# BLHP2432_H24-Fan-Controller.net
KiCad netlist of a schematic drawn in Altium Designer
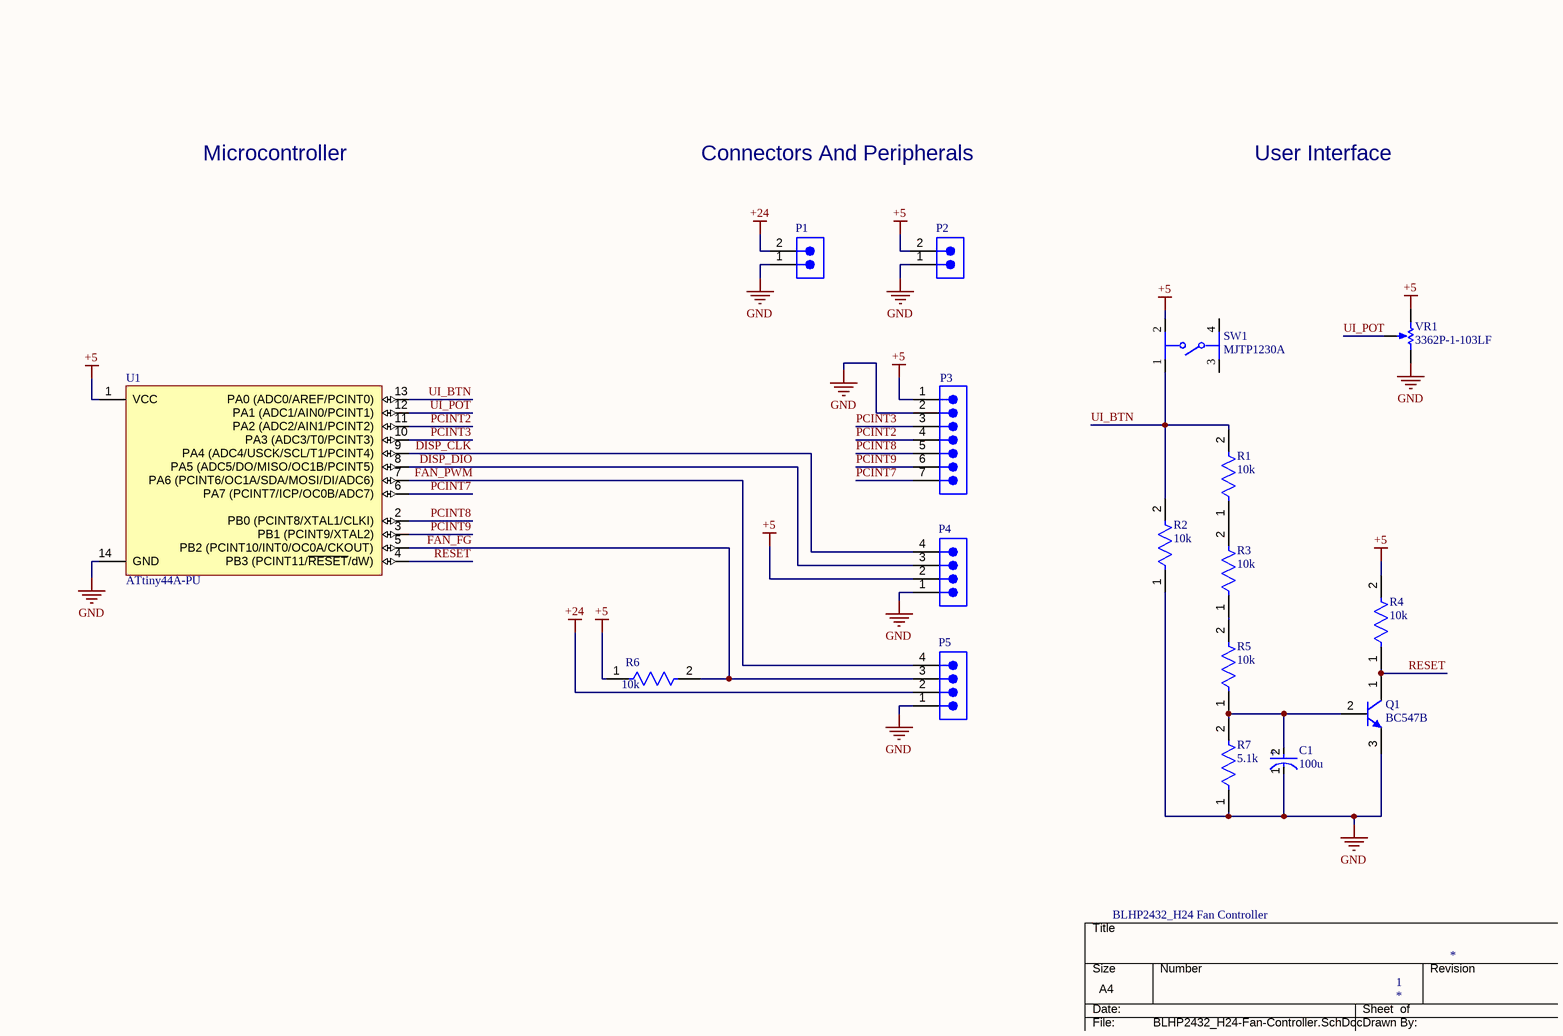
[diagram p0: BLHP2432_H24-Fan-Controller.SchDoc]

(export (version "E")
  (design (tool "Eeschema 10.0.6"))
  (components
    (comp (ref "C1")
      (value "100u")
      (footprint "FP-UHW1E222MHD-MFG")
      (description "CAP ALUM 2200UF 20% 25V RADIAL")
      (fields (field (name "TOLERANCE") "20%"))
      (libsource (lib "Altium Content Vault") (part "203bc49f2ac43e59fd269a8c329ed05"))
    )
    (comp (ref "P1")
      (value "TSW-102-26-G-S")
      (footprint "SMTC-TSW-102-26-XX-S")
      (description "0.025\" SQ Post Header, Through-hole, Vertical, -55 to 125 degC, 2.54 mm Pitch, 2-Pin, Male, RoHS")
      (fields (field (name "MANUFACTURER") "Samtec"))
      (libsource (lib "Altium Content Vault") (part "SMTC-TSW-102-X-X-S-X"))
    )
    (comp (ref "P2")
      (value "TSW-102-26-G-S")
      (footprint "SMTC-TSW-102-26-XX-S")
      (description "0.025\" SQ Post Header, Through-hole, Vertical, -55 to 125 degC, 2.54 mm Pitch, 2-Pin, Male, RoHS")
      (fields (field (name "MANUFACTURER") "Samtec"))
      (libsource (lib "Altium Content Vault") (part "SMTC-TSW-102-X-X-S-X"))
    )
    (comp (ref "P3")
      (value "61300711021")
      (footprint "61300711021")
      (description "THT Angled Pin Header WR-PHD, Pitch 2.54 mm, Single Row, 7 pins")
      (libsource (lib "Altium Content Vault") (part "Header_Male_1R_07P"))
    )
    (comp (ref "P4")
      (value "~")
      (footprint "SMTC-TSW-104-08-X-S")
      (description "0.025\" SQ Post Header, Through-hole, Vertical, -55 to 125 degC, 2.54 mm Pitch, 4-Pin, Male, RoHS")
      (fields (field (name "MANUFACTURER") "Samtec") (field (name "PARTNUMBER") "TSW-104-08-G-S"))
      (libsource (lib "Altium Content Vault") (part "SMTC-TSW-104-08-X-S"))
    )
    (comp (ref "P5")
      (value "~")
      (footprint "SMTC-TSW-104-08-X-S")
      (description "0.025\" SQ Post Header, Through-hole, Vertical, -55 to 125 degC, 2.54 mm Pitch, 4-Pin, Male, RoHS")
      (fields (field (name "MANUFACTURER") "Samtec") (field (name "PARTNUMBER") "TSW-104-08-G-S"))
      (libsource (lib "Altium Content Vault") (part "SMTC-TSW-104-08-X-S"))
    )
    (comp (ref "Q1")
      (value "BC547B")
      (footprint "ONSC-TO-92-3-29-11")
      (description "Amplifier Transistor, NPN Silicon, 3-Pin TO-92, Bulk Box")
      (fields (field (name "MANUFACTURER") "On Semiconductor"))
      (libsource (lib "Altium Content Vault") (part "ONSC-NPN-C1B2E3-3"))
    )
    (comp (ref "R1")
      (value "10k")
      (footprint "FP-MBB0207-MFG")
      (description "RES 10K OHM 0.6W 1% AXIAL")
      (fields (field (name "TOLERANCE") "1%"))
      (libsource (lib "Altium Content Vault") (part "1029c3af85768c4190bb7ad29bc67b5"))
    )
    (comp (ref "R2")
      (value "10k")
      (footprint "FP-MBB0207-MFG")
      (description "RES 10K OHM 0.6W 1% AXIAL")
      (fields (field (name "TOLERANCE") "1%"))
      (libsource (lib "Altium Content Vault") (part "1029c3af85768c4190bb7ad29bc67b5"))
    )
    (comp (ref "R3")
      (value "10k")
      (footprint "FP-MBB0207-MFG")
      (description "RES 10K OHM 0.6W 1% AXIAL")
      (fields (field (name "TOLERANCE") "1%"))
      (libsource (lib "Altium Content Vault") (part "1029c3af85768c4190bb7ad29bc67b5"))
    )
    (comp (ref "R4")
      (value "10k")
      (footprint "FP-MBB0207-MFG")
      (description "RES 10K OHM 0.6W 1% AXIAL")
      (fields (field (name "TOLERANCE") "1%"))
      (libsource (lib "Altium Content Vault") (part "1029c3af85768c4190bb7ad29bc67b5"))
    )
    (comp (ref "R5")
      (value "10k")
      (footprint "FP-MBB0207-MFG")
      (description "RES 10K OHM 0.6W 1% AXIAL")
      (fields (field (name "TOLERANCE") "1%"))
      (libsource (lib "Altium Content Vault") (part "1029c3af85768c4190bb7ad29bc67b5"))
    )
    (comp (ref "R6")
      (value "10k")
      (footprint "FP-MBB0207-MFG")
      (description "RES 10K OHM 0.6W 1% AXIAL")
      (fields (field (name "TOLERANCE") "1%"))
      (libsource (lib "Altium Content Vault") (part "1029c3af85768c4190bb7ad29bc67b5"))
    )
    (comp (ref "R7")
      (value "5.1k")
      (footprint "FP-MBB0207-MFG")
      (description "RES 10K OHM 0.6W 1% AXIAL")
      (fields (field (name "TOLERANCE") "1%"))
      (libsource (lib "Altium Content Vault") (part "1029c3af85768c4190bb7ad29bc67b5"))
    )
    (comp (ref "SW1")
      (value "MJTP1230A")
      (footprint "FP-MJTP1230A-MFG")
      (description "SWITCH TACTILE SPST-NO 0.05A 12V")
      (libsource (lib "Altium Content Vault") (part "1adf0dd01260c80cf25a44bfd6b99ba"))
    )
    (comp (ref "U1")
      (value "ATtiny44A-PU")
      (footprint "14P3")
      (libsource (lib "Altium Content Vault") (part "MC-8B-ATTINY24V-IL14"))
    )
    (comp (ref "VR1")
      (value "3362P-1-103LF")
      (footprint "BOUR-3362P")
      (description "Square Trimpot(R) Trimming Potentiometer, 10 KOhm, 300 V, -55 to 125 degC, 3-Pin THD, RoHS, Tube")
      (fields (field (name "TOLERANCE") "1%"))
      (libsource (lib "Altium Content Vault") (part "RES-POT-3"))
    )
  )
  (nets
    (net (code "1") (name "+5") (class "Default")
      (node (ref "P2") (pin "2") (pinfunction "2_2") (pintype "passive"))
      (node (ref "P3") (pin "1") (pinfunction "1_1") (pintype "passive"))
      (node (ref "P4") (pin "2") (pinfunction "2_2") (pintype "passive"))
      (node (ref "R4") (pin "2") (pinfunction "2_2") (pintype "passive"))
      (node (ref "R6") (pin "1") (pinfunction "1_1") (pintype "passive"))
      (node (ref "SW1") (pin "2") (pinfunction "2_2") (pintype "passive"))
      (node (ref "U1") (pin "1") (pinfunction "VCC_1") (pintype "power_in"))
      (node (ref "VR1") (pin "1") (pinfunction "CCW_1") (pintype "passive"))
    )
    (net (code "2") (name "+24") (class "Default")
      (node (ref "P1") (pin "2") (pinfunction "2_2") (pintype "passive"))
      (node (ref "P5") (pin "2") (pinfunction "2_2") (pintype "passive"))
    )
    (net (code "3") (name "/DISP_CLK") (class "Default")
      (node (ref "P4") (pin "4") (pinfunction "4_4") (pintype "passive"))
      (node (ref "U1") (pin "9") (pinfunction "PA4_(ADC4/USCK/SCL/T1/PCINT4)_9") (pintype "bidirectional"))
    )
    (net (code "4") (name "/DISP_DIO") (class "Default")
      (node (ref "P4") (pin "3") (pinfunction "3_3") (pintype "passive"))
      (node (ref "U1") (pin "8") (pinfunction "PA5_(ADC5/DO/MISO/OC1B/PCINT5)_8") (pintype "bidirectional"))
    )
    (net (code "5") (name "/FAN_FG") (class "Default")
      (node (ref "P5") (pin "3") (pinfunction "3_3") (pintype "passive"))
      (node (ref "R6") (pin "2") (pinfunction "2_2") (pintype "passive"))
      (node (ref "U1") (pin "5") (pinfunction "PB2_(PCINT10/INT0/OC0A/CKOUT)_5") (pintype "bidirectional"))
    )
    (net (code "6") (name "/FAN_PWM") (class "Default")
      (node (ref "P5") (pin "4") (pinfunction "4_4") (pintype "passive"))
      (node (ref "U1") (pin "7") (pinfunction "PA6_(PCINT6/OC1A/SDA/MOSI/DI/ADC6)_7") (pintype "bidirectional"))
    )
    (net (code "7") (name "/PCINT2") (class "Default")
      (node (ref "P3") (pin "4") (pinfunction "4_4") (pintype "passive"))
      (node (ref "U1") (pin "11") (pinfunction "PA2_(ADC2/AIN1/PCINT2)_11") (pintype "bidirectional"))
    )
    (net (code "8") (name "/PCINT3") (class "Default")
      (node (ref "P3") (pin "3") (pinfunction "3_3") (pintype "passive"))
      (node (ref "U1") (pin "10") (pinfunction "PA3_(ADC3/T0/PCINT3)_10") (pintype "bidirectional"))
    )
    (net (code "9") (name "/PCINT7") (class "Default")
      (node (ref "P3") (pin "7") (pinfunction "7_7") (pintype "passive"))
      (node (ref "U1") (pin "6") (pinfunction "PA7_(PCINT7/ICP/OC0B/ADC7)_6") (pintype "bidirectional"))
    )
    (net (code "10") (name "/PCINT8") (class "Default")
      (node (ref "P3") (pin "5") (pinfunction "5_5") (pintype "passive"))
      (node (ref "U1") (pin "2") (pinfunction "PB0_(PCINT8/XTAL1/CLKI)_2") (pintype "bidirectional"))
    )
    (net (code "11") (name "/PCINT9") (class "Default")
      (node (ref "P3") (pin "6") (pinfunction "6_6") (pintype "passive"))
      (node (ref "U1") (pin "3") (pinfunction "PB1_(PCINT9/XTAL2)_3") (pintype "bidirectional"))
    )
    (net (code "12") (name "/RESET") (class "Default")
      (node (ref "Q1") (pin "1") (pinfunction "C_1") (pintype "passive"))
      (node (ref "R4") (pin "1") (pinfunction "1_1") (pintype "passive"))
      (node (ref "U1") (pin "4") (pinfunction "PB3_(PCINT11/~{RESET}/dW)_4") (pintype "bidirectional"))
    )
    (net (code "13") (name "/UI_BTN") (class "Default")
      (node (ref "R1") (pin "2") (pinfunction "2_2") (pintype "passive"))
      (node (ref "R2") (pin "2") (pinfunction "2_2") (pintype "passive"))
      (node (ref "SW1") (pin "1") (pinfunction "1_1") (pintype "passive"))
      (node (ref "U1") (pin "13") (pinfunction "PA0_(ADC0/AREF/PCINT0)_13") (pintype "bidirectional"))
    )
    (net (code "14") (name "/UI_POT") (class "Default")
      (node (ref "U1") (pin "12") (pinfunction "PA1_(ADC1/AIN0/PCINT1)_12") (pintype "bidirectional"))
      (node (ref "VR1") (pin "2") (pinfunction "S_2") (pintype "passive"))
    )
    (net (code "15") (name "GND") (class "Default")
      (node (ref "C1") (pin "1") (pinfunction "C_1") (pintype "passive"))
      (node (ref "P1") (pin "1") (pinfunction "1_1") (pintype "passive"))
      (node (ref "P2") (pin "1") (pinfunction "1_1") (pintype "passive"))
      (node (ref "P3") (pin "2") (pinfunction "2_2") (pintype "passive"))
      (node (ref "P4") (pin "1") (pinfunction "1_1") (pintype "passive"))
      (node (ref "P5") (pin "1") (pinfunction "1_1") (pintype "passive"))
      (node (ref "Q1") (pin "3") (pinfunction "E_3") (pintype "passive"))
      (node (ref "R2") (pin "1") (pinfunction "1_1") (pintype "passive"))
      (node (ref "R7") (pin "1") (pinfunction "1_1") (pintype "passive"))
      (node (ref "U1") (pin "14") (pinfunction "GND_14") (pintype "power_in"))
      (node (ref "VR1") (pin "3") (pinfunction "CW_3") (pintype "passive"))
    )
    (net (code "16") (name "Net-(C1-A)") (class "Default")
      (node (ref "C1") (pin "2") (pinfunction "A_2") (pintype "passive"))
      (node (ref "Q1") (pin "2") (pinfunction "B_2") (pintype "passive"))
      (node (ref "R5") (pin "1") (pinfunction "1_1") (pintype "passive"))
      (node (ref "R7") (pin "2") (pinfunction "2_2") (pintype "passive"))
    )
    (net (code "17") (name "Net-(R1-Pad1)") (class "Default")
      (node (ref "R1") (pin "1") (pinfunction "1_1") (pintype "passive"))
      (node (ref "R3") (pin "2") (pinfunction "2_2") (pintype "passive"))
    )
    (net (code "18") (name "Net-(R3-Pad1)") (class "Default")
      (node (ref "R3") (pin "1") (pinfunction "1_1") (pintype "passive"))
      (node (ref "R5") (pin "2") (pinfunction "2_2") (pintype "passive"))
    )
    (net (code "19") (name "unconnected-(SW1-Pad3)") (class "Default")
      (node (ref "SW1") (pin "3") (pinfunction "3_3") (pintype "passive"))
    )
    (net (code "20") (name "unconnected-(SW1-Pad4)") (class "Default")
      (node (ref "SW1") (pin "4") (pinfunction "4_4") (pintype "passive"))
    )
  )
)
